# test-cell-one-shot.net
KiCad netlist of a schematic drawn in EAGLE
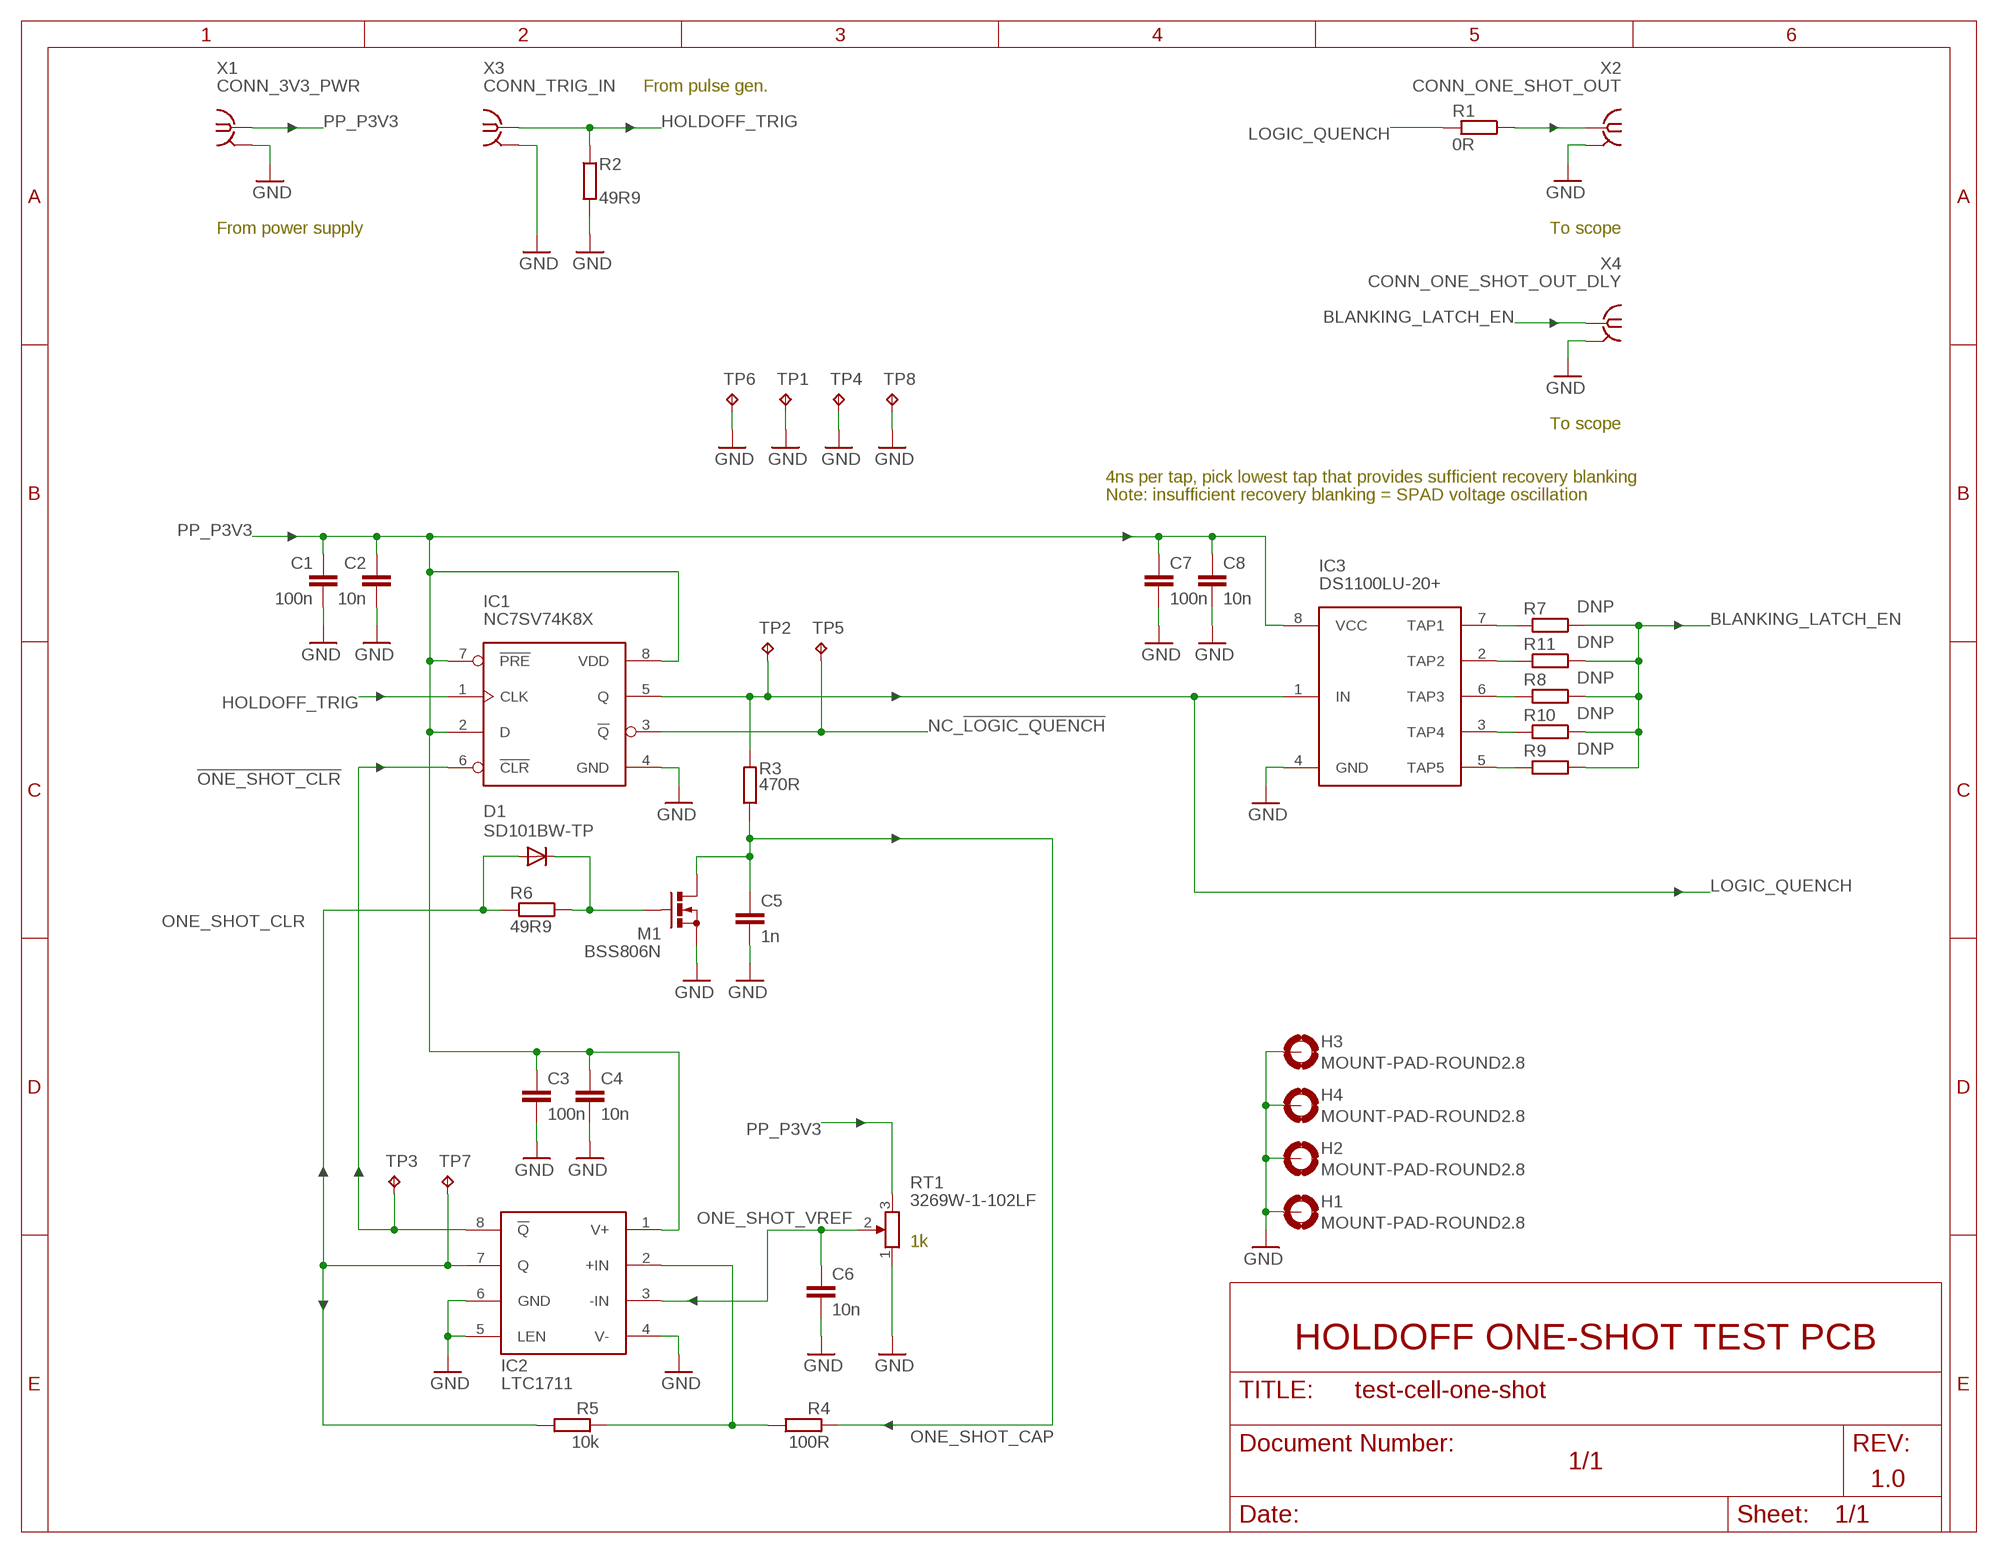
[diagram p0: schematic, sheet 1]

(export (version "E")
  (design (tool "Eeschema 10.0.6"))
  (components
    (comp (ref "C1")
      (value "100n")
      (footprint "eagle-import:C0402")
      (libsource (lib "eagle-import") (part "C-EUC0402"))
    )
    (comp (ref "C2")
      (value "10n")
      (footprint "eagle-import:C0402")
      (libsource (lib "eagle-import") (part "C-EUC0402"))
    )
    (comp (ref "C3")
      (value "100n")
      (footprint "eagle-import:C0402")
      (libsource (lib "eagle-import") (part "C-EUC0402"))
    )
    (comp (ref "C4")
      (value "10n")
      (footprint "eagle-import:C0402")
      (libsource (lib "eagle-import") (part "C-EUC0402"))
    )
    (comp (ref "C5")
      (value "1n")
      (footprint "eagle-import:C0402")
      (libsource (lib "eagle-import") (part "C-EUC0402"))
    )
    (comp (ref "C6")
      (value "10n")
      (footprint "eagle-import:C0402")
      (libsource (lib "eagle-import") (part "C-EUC0402"))
    )
    (comp (ref "C7")
      (value "100n")
      (footprint "eagle-import:C0402")
      (libsource (lib "eagle-import") (part "C-EUC0402"))
    )
    (comp (ref "C8")
      (value "10n")
      (footprint "eagle-import:C0402")
      (libsource (lib "eagle-import") (part "C-EUC0402"))
    )
    (comp (ref "D1")
      (value "SD101BW-TP")
      (footprint "eagle-import:SOD123")
      (libsource (lib "eagle-import") (part "DIODE-SOD123"))
    )
    (comp (ref "H1")
      (value "MOUNT-PAD-ROUND2.8")
      (footprint "eagle-import:2,8-PAD")
      (libsource (lib "eagle-import") (part "MOUNT-PAD-ROUND2.8"))
    )
    (comp (ref "H2")
      (value "MOUNT-PAD-ROUND2.8")
      (footprint "eagle-import:2,8-PAD")
      (libsource (lib "eagle-import") (part "MOUNT-PAD-ROUND2.8"))
    )
    (comp (ref "H3")
      (value "MOUNT-PAD-ROUND2.8")
      (footprint "eagle-import:2,8-PAD")
      (libsource (lib "eagle-import") (part "MOUNT-PAD-ROUND2.8"))
    )
    (comp (ref "H4")
      (value "MOUNT-PAD-ROUND2.8")
      (footprint "eagle-import:2,8-PAD")
      (libsource (lib "eagle-import") (part "MOUNT-PAD-ROUND2.8"))
    )
    (comp (ref "IC1")
      (value "NC7SV74K8X")
      (footprint "eagle-import:US8_3.1MM_JDEC_MO-187")
      (libsource (lib "eagle-import") (part "NC7SV74K8X"))
    )
    (comp (ref "IC2")
      (value "LTC1711")
      (footprint "eagle-import:US8_3.1MM_JDEC_MO-187")
      (libsource (lib "eagle-import") (part "LTC1711"))
    )
    (comp (ref "IC3")
      (value "DS1100LU-20+")
      (footprint "eagle-import:US8_3.1MM_JDEC_MO-187")
      (libsource (lib "eagle-import") (part "DS1100L"))
    )
    (comp (ref "M1")
      (value "BSS806N")
      (footprint "eagle-import:SOT23R_INFINEON")
      (libsource (lib "eagle-import") (part "BSS806N"))
    )
    (comp (ref "R1")
      (value "0R")
      (footprint "eagle-import:R0402")
      (libsource (lib "eagle-import") (part "R-EU_R0402"))
    )
    (comp (ref "R2")
      (value "49R9")
      (footprint "eagle-import:R0603")
      (libsource (lib "eagle-import") (part "R-EU_R0603"))
    )
    (comp (ref "R3")
      (value "470R")
      (footprint "eagle-import:R0402")
      (libsource (lib "eagle-import") (part "R-EU_R0402"))
    )
    (comp (ref "R4")
      (value "100R")
      (footprint "eagle-import:R0402")
      (libsource (lib "eagle-import") (part "R-EU_R0402"))
    )
    (comp (ref "R5")
      (value "10k")
      (footprint "eagle-import:R0402")
      (libsource (lib "eagle-import") (part "R-EU_R0402"))
    )
    (comp (ref "R6")
      (value "49R9")
      (footprint "eagle-import:R0402")
      (libsource (lib "eagle-import") (part "R-EU_R0402"))
    )
    (comp (ref "R7")
      (value "DNP")
      (footprint "eagle-import:R0402")
      (libsource (lib "eagle-import") (part "R-EU_R0402"))
    )
    (comp (ref "R8")
      (value "DNP")
      (footprint "eagle-import:R0402")
      (libsource (lib "eagle-import") (part "R-EU_R0402"))
    )
    (comp (ref "R9")
      (value "DNP")
      (footprint "eagle-import:R0402")
      (libsource (lib "eagle-import") (part "R-EU_R0402"))
    )
    (comp (ref "R10")
      (value "DNP")
      (footprint "eagle-import:R0402")
      (libsource (lib "eagle-import") (part "R-EU_R0402"))
    )
    (comp (ref "R11")
      (value "DNP")
      (footprint "eagle-import:R0402")
      (libsource (lib "eagle-import") (part "R-EU_R0402"))
    )
    (comp (ref "RT1")
      (value "3269W-1-102LF")
      (footprint "eagle-import:3269W")
      (libsource (lib "eagle-import") (part "BOURNS_3269WX"))
    )
    (comp (ref "TP1")
      (value "TPTP10R")
      (footprint "eagle-import:TP10R")
      (libsource (lib "eagle-import") (part "TPTP10R"))
    )
    (comp (ref "TP2")
      (value "TPTP10R")
      (footprint "eagle-import:TP10R")
      (libsource (lib "eagle-import") (part "TPTP10R"))
    )
    (comp (ref "TP3")
      (value "TPTP10R")
      (footprint "eagle-import:TP10R")
      (libsource (lib "eagle-import") (part "TPTP10R"))
    )
    (comp (ref "TP4")
      (value "TPTP10R")
      (footprint "eagle-import:TP10R")
      (libsource (lib "eagle-import") (part "TPTP10R"))
    )
    (comp (ref "TP5")
      (value "TPTP10R")
      (footprint "eagle-import:TP10R")
      (libsource (lib "eagle-import") (part "TPTP10R"))
    )
    (comp (ref "TP6")
      (value "TPTP10R")
      (footprint "eagle-import:TP10R")
      (libsource (lib "eagle-import") (part "TPTP10R"))
    )
    (comp (ref "TP7")
      (value "TPTP10R")
      (footprint "eagle-import:TP10R")
      (libsource (lib "eagle-import") (part "TPTP10R"))
    )
    (comp (ref "TP8")
      (value "TPTP10R")
      (footprint "eagle-import:TP10R")
      (libsource (lib "eagle-import") (part "TPTP10R"))
    )
    (comp (ref "X1")
      (value "CONN_3V3_PWR")
      (footprint "eagle-import:J502-ND-142-0711-871_876")
      (fields (field (name "MF") "JOHNSON COMPONENTS") (field (name "MPN") "142-0711-871"))
      (libsource (lib "eagle-import") (part "SMA-142-0711-871/876"))
    )
    (comp (ref "X2")
      (value "CONN_ONE_SHOT_OUT")
      (footprint "eagle-import:J502-ND-142-0711-871_876")
      (fields (field (name "MF") "JOHNSON COMPONENTS") (field (name "MPN") "142-0711-871"))
      (libsource (lib "eagle-import") (part "SMA-142-0711-871/876"))
    )
    (comp (ref "X3")
      (value "CONN_TRIG_IN")
      (footprint "eagle-import:J502-ND-142-0711-871_876")
      (fields (field (name "MF") "JOHNSON COMPONENTS") (field (name "MPN") "142-0711-871"))
      (libsource (lib "eagle-import") (part "SMA-142-0711-871/876"))
    )
    (comp (ref "X4")
      (value "CONN_ONE_SHOT_OUT_DLY")
      (footprint "eagle-import:J502-ND-142-0711-871_876")
      (fields (field (name "MF") "JOHNSON COMPONENTS") (field (name "MPN") "142-0711-871"))
      (libsource (lib "eagle-import") (part "SMA-142-0711-871/876"))
    )
  )
  (nets
    (net (code "1") (name "/BLANKING_LATCH_EN") (class "Default")
      (node (ref "R10") (pin "1") (pinfunction "1_1") (pintype "passive"))
      (node (ref "R11") (pin "1") (pinfunction "1_1") (pintype "passive"))
      (node (ref "R7") (pin "1") (pinfunction "1_1") (pintype "passive"))
      (node (ref "R8") (pin "1") (pinfunction "1_1") (pintype "passive"))
      (node (ref "R9") (pin "1") (pinfunction "1_1") (pintype "passive"))
      (node (ref "X4") (pin "1") (pinfunction "1_1") (pintype "passive"))
    )
    (net (code "2") (name "/HOLDOFF_TRIG") (class "Default")
      (node (ref "IC1") (pin "1") (pinfunction "CLK_1") (pintype "bidirectional"))
      (node (ref "R2") (pin "1") (pinfunction "1_1") (pintype "passive"))
      (node (ref "X3") (pin "1") (pinfunction "1_1") (pintype "passive"))
    )
    (net (code "3") (name "/LOGIC_QUENCH") (class "Default")
      (node (ref "IC1") (pin "5") (pinfunction "Q_5") (pintype "bidirectional"))
      (node (ref "IC3") (pin "1") (pinfunction "IN_1") (pintype "bidirectional"))
      (node (ref "R1") (pin "2") (pinfunction "2_2") (pintype "passive"))
      (node (ref "R3") (pin "2") (pinfunction "2_2") (pintype "passive"))
      (node (ref "TP2") (pin "TP") (pinfunction "TP_TP") (pintype "input"))
    )
    (net (code "4") (name "/NC_~{LOGIC_QUENCH}") (class "Default")
      (node (ref "IC1") (pin "3") (pinfunction "~{Q}_3") (pintype "bidirectional"))
      (node (ref "TP5") (pin "TP") (pinfunction "TP_TP") (pintype "input"))
    )
    (net (code "5") (name "/ONE_SHOT_CAP") (class "Default")
      (node (ref "C5") (pin "1") (pinfunction "1_1") (pintype "passive"))
      (node (ref "M1") (pin "3") (pinfunction "D_3") (pintype "passive"))
      (node (ref "R3") (pin "1") (pinfunction "1_1") (pintype "passive"))
      (node (ref "R4") (pin "2") (pinfunction "2_2") (pintype "passive"))
    )
    (net (code "6") (name "/ONE_SHOT_CLR") (class "Default")
      (node (ref "D1") (pin "A") (pinfunction "A_A") (pintype "passive"))
      (node (ref "IC2") (pin "7") (pinfunction "Q_7") (pintype "bidirectional"))
      (node (ref "R5") (pin "1") (pinfunction "1_1") (pintype "passive"))
      (node (ref "R6") (pin "2") (pinfunction "2_2") (pintype "passive"))
      (node (ref "TP7") (pin "TP") (pinfunction "TP_TP") (pintype "input"))
    )
    (net (code "7") (name "/ONE_SHOT_VREF") (class "Default")
      (node (ref "C6") (pin "1") (pinfunction "1_1") (pintype "passive"))
      (node (ref "IC2") (pin "3") (pinfunction "-IN_3") (pintype "bidirectional"))
      (node (ref "RT1") (pin "2") (pinfunction "2_2") (pintype "bidirectional"))
    )
    (net (code "8") (name "/PP_P3V3") (class "Default")
      (node (ref "C1") (pin "1") (pinfunction "1_1") (pintype "passive"))
      (node (ref "C2") (pin "1") (pinfunction "1_1") (pintype "passive"))
      (node (ref "C3") (pin "1") (pinfunction "1_1") (pintype "passive"))
      (node (ref "C4") (pin "1") (pinfunction "1_1") (pintype "passive"))
      (node (ref "C7") (pin "1") (pinfunction "1_1") (pintype "passive"))
      (node (ref "C8") (pin "1") (pinfunction "1_1") (pintype "passive"))
      (node (ref "IC1") (pin "2") (pinfunction "D_2") (pintype "bidirectional"))
      (node (ref "IC1") (pin "7") (pinfunction "~{PRE}_7") (pintype "bidirectional"))
      (node (ref "IC1") (pin "8") (pinfunction "VDD_8") (pintype "bidirectional"))
      (node (ref "IC2") (pin "1") (pinfunction "V+_1") (pintype "bidirectional"))
      (node (ref "IC3") (pin "8") (pinfunction "VCC_8") (pintype "bidirectional"))
      (node (ref "RT1") (pin "3") (pinfunction "3_3") (pintype "bidirectional"))
      (node (ref "X1") (pin "1") (pinfunction "1_1") (pintype "passive"))
    )
    (net (code "9") (name "/~{ONE_SHOT_CLR}") (class "Default")
      (node (ref "IC1") (pin "6") (pinfunction "~{CLR}_6") (pintype "bidirectional"))
      (node (ref "IC2") (pin "8") (pinfunction "~{Q}_8") (pintype "bidirectional"))
      (node (ref "TP3") (pin "TP") (pinfunction "TP_TP") (pintype "input"))
    )
    (net (code "10") (name "GND") (class "Default")
      (node (ref "C1") (pin "2") (pinfunction "2_2") (pintype "passive"))
      (node (ref "C2") (pin "2") (pinfunction "2_2") (pintype "passive"))
      (node (ref "C3") (pin "2") (pinfunction "2_2") (pintype "passive"))
      (node (ref "C4") (pin "2") (pinfunction "2_2") (pintype "passive"))
      (node (ref "C5") (pin "2") (pinfunction "2_2") (pintype "passive"))
      (node (ref "C6") (pin "2") (pinfunction "2_2") (pintype "passive"))
      (node (ref "C7") (pin "2") (pinfunction "2_2") (pintype "passive"))
      (node (ref "C8") (pin "2") (pinfunction "2_2") (pintype "passive"))
      (node (ref "H1") (pin "B2,8") (pinfunction "MOUNT_B2,8") (pintype "passive"))
      (node (ref "H2") (pin "B2,8") (pinfunction "MOUNT_B2,8") (pintype "passive"))
      (node (ref "H3") (pin "B2,8") (pinfunction "MOUNT_B2,8") (pintype "passive"))
      (node (ref "H4") (pin "B2,8") (pinfunction "MOUNT_B2,8") (pintype "passive"))
      (node (ref "IC1") (pin "4") (pinfunction "GND_4") (pintype "bidirectional"))
      (node (ref "IC2") (pin "4") (pinfunction "V-_4") (pintype "bidirectional"))
      (node (ref "IC2") (pin "5") (pinfunction "LEN_5") (pintype "bidirectional"))
      (node (ref "IC2") (pin "6") (pinfunction "GND_6") (pintype "bidirectional"))
      (node (ref "IC3") (pin "4") (pinfunction "GND_4") (pintype "bidirectional"))
      (node (ref "M1") (pin "2") (pinfunction "S_2") (pintype "passive"))
      (node (ref "R2") (pin "2") (pinfunction "2_2") (pintype "passive"))
      (node (ref "RT1") (pin "1") (pinfunction "1_1") (pintype "bidirectional"))
      (node (ref "TP1") (pin "TP") (pinfunction "TP_TP") (pintype "input"))
      (node (ref "TP4") (pin "TP") (pinfunction "TP_TP") (pintype "input"))
      (node (ref "TP6") (pin "TP") (pinfunction "TP_TP") (pintype "input"))
      (node (ref "TP8") (pin "TP") (pinfunction "TP_TP") (pintype "input"))
      (node (ref "X1") (pin "G@1") (pinfunction "GND_G@1") (pintype "power_in"))
      (node (ref "X2") (pin "G@1") (pinfunction "GND_G@1") (pintype "power_in"))
      (node (ref "X3") (pin "G@1") (pinfunction "GND_G@1") (pintype "power_in"))
      (node (ref "X4") (pin "G@1") (pinfunction "GND_G@1") (pintype "power_in"))
    )
    (net (code "11") (name "Net-(IC2-+IN)") (class "Default")
      (node (ref "IC2") (pin "2") (pinfunction "+IN_2") (pintype "bidirectional"))
      (node (ref "R4") (pin "1") (pinfunction "1_1") (pintype "passive"))
      (node (ref "R5") (pin "2") (pinfunction "2_2") (pintype "passive"))
    )
    (net (code "12") (name "Net-(IC3-TAP1)") (class "Default")
      (node (ref "IC3") (pin "7") (pinfunction "TAP1_7") (pintype "bidirectional"))
      (node (ref "R7") (pin "2") (pinfunction "2_2") (pintype "passive"))
    )
    (net (code "13") (name "Net-(IC3-TAP2)") (class "Default")
      (node (ref "IC3") (pin "2") (pinfunction "TAP2_2") (pintype "bidirectional"))
      (node (ref "R11") (pin "2") (pinfunction "2_2") (pintype "passive"))
    )
    (net (code "14") (name "Net-(IC3-TAP3)") (class "Default")
      (node (ref "IC3") (pin "6") (pinfunction "TAP3_6") (pintype "bidirectional"))
      (node (ref "R8") (pin "2") (pinfunction "2_2") (pintype "passive"))
    )
    (net (code "15") (name "Net-(IC3-TAP4)") (class "Default")
      (node (ref "IC3") (pin "3") (pinfunction "TAP4_3") (pintype "bidirectional"))
      (node (ref "R10") (pin "2") (pinfunction "2_2") (pintype "passive"))
    )
    (net (code "16") (name "Net-(IC3-TAP5)") (class "Default")
      (node (ref "IC3") (pin "5") (pinfunction "TAP5_5") (pintype "bidirectional"))
      (node (ref "R9") (pin "2") (pinfunction "2_2") (pintype "passive"))
    )
    (net (code "17") (name "Net-(M1-G)") (class "Default")
      (node (ref "D1") (pin "C") (pinfunction "C_C") (pintype "passive"))
      (node (ref "M1") (pin "1") (pinfunction "G_1") (pintype "passive"))
      (node (ref "R6") (pin "1") (pinfunction "1_1") (pintype "passive"))
    )
    (net (code "18") (name "Net-(R1-Pad1)") (class "Default")
      (node (ref "R1") (pin "1") (pinfunction "1_1") (pintype "passive"))
      (node (ref "X2") (pin "1") (pinfunction "1_1") (pintype "passive"))
    )
  )
)
